# PC5_AudioOutput.net
KiCad netlist of a schematic drawn in Altium Designer
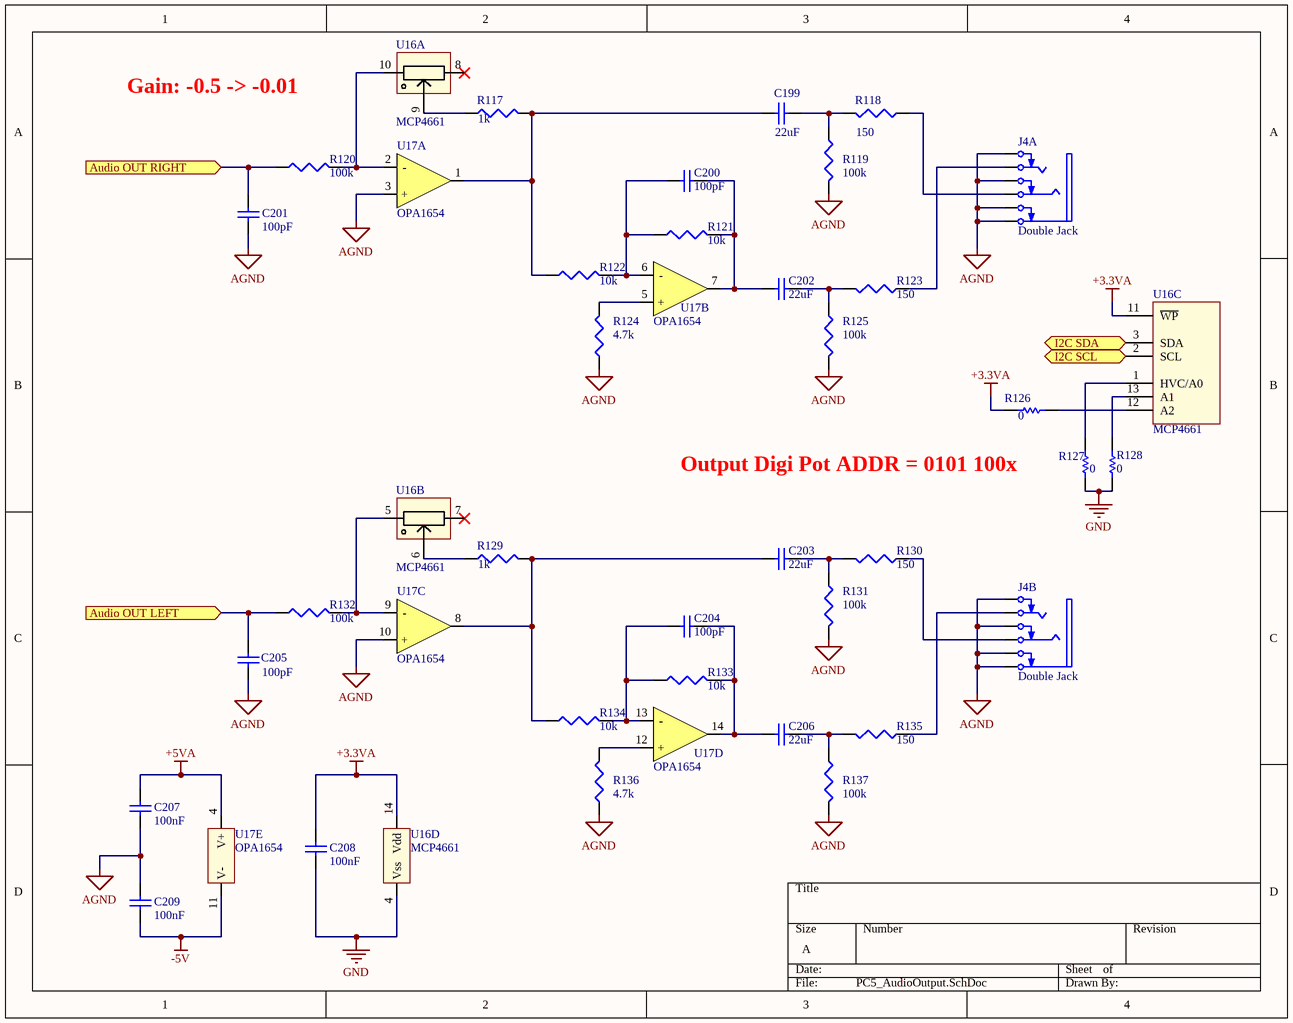
[diagram p0: PC5_AudioOutput.SchDoc]

(export (version "E")
  (design (tool "Eeschema 10.0.6"))
  (components
    (comp (ref "C199")
      (value "22uF")
      (footprint "CAPC1608X08")
      (description "Capacitor")
      (fields (field (name "Comment") "Cap 22uF"))
      (libsource (lib "Michel") (part "Cap Semi"))
    )
    (comp (ref "C200")
      (value "100pF")
      (footprint "CAPC1608X08")
      (description "Capacitor")
      (fields (field (name "Comment") "Cap 100pF"))
      (libsource (lib "Michel") (part "Cap Semi"))
    )
    (comp (ref "C201")
      (value "100pF")
      (footprint "CAPC1608X08")
      (description "Capacitor")
      (fields (field (name "Comment") "Cap 100pF"))
      (libsource (lib "Michel") (part "Cap Semi"))
    )
    (comp (ref "C202")
      (value "22uF")
      (footprint "CAPC1608X08")
      (description "Capacitor")
      (fields (field (name "Comment") "Cap 22uF"))
      (libsource (lib "Michel") (part "Cap Semi"))
    )
    (comp (ref "C203")
      (value "22uF")
      (footprint "CAPC1608X08")
      (description "Capacitor")
      (fields (field (name "Comment") "Cap 22uF"))
      (libsource (lib "Michel") (part "Cap Semi"))
    )
    (comp (ref "C204")
      (value "100pF")
      (footprint "CAPC1608X08")
      (description "Capacitor")
      (fields (field (name "Comment") "Cap 100pF"))
      (libsource (lib "Michel") (part "Cap Semi"))
    )
    (comp (ref "C205")
      (value "100pF")
      (footprint "CAPC1608X08")
      (description "Capacitor")
      (fields (field (name "Comment") "Cap 100pF"))
      (libsource (lib "Michel") (part "Cap Semi"))
    )
    (comp (ref "C206")
      (value "22uF")
      (footprint "CAPC1608X08")
      (description "Capacitor")
      (fields (field (name "Comment") "Cap 22uF"))
      (libsource (lib "Michel") (part "Cap Semi"))
    )
    (comp (ref "C207")
      (value "100nF")
      (footprint "CAPC1608X08")
      (description "Capacitor")
      (fields (field (name "Comment") "Cap 100nF"))
      (libsource (lib "Michel") (part "Cap Semi"))
    )
    (comp (ref "C208")
      (value "100nF")
      (footprint "CAPC1608X08")
      (description "Capacitor")
      (fields (field (name "Comment") "Cap 100nF"))
      (libsource (lib "Michel") (part "Cap Semi"))
    )
    (comp (ref "C209")
      (value "100nF")
      (footprint "CAPC1608X08")
      (description "Capacitor")
      (fields (field (name "Comment") "Cap 100nF"))
      (libsource (lib "Michel") (part "Cap Semi"))
    )
    (comp (ref "J4")
      (value "Double Jack")
      (footprint "Amphenol_ACJS-MHDC")
      (description "Dual Jack stereo bypassed")
      (libsource (lib "") (part "Dual TRS Jack Bypassed_1"))
    )
    (comp (ref "R117")
      (value "1k")
      (footprint "RESC1608X05")
      (description "Resistor")
      (fields (field (name "Comment") "Res 1k"))
      (libsource (lib "Michel") (part "Res3"))
    )
    (comp (ref "R118")
      (value "150")
      (footprint "RESC1608X05")
      (description "Capacitor")
      (fields (field (name "Comment") "Cap 150"))
      (libsource (lib "Michel") (part "Res3"))
    )
    (comp (ref "R119")
      (value "100k")
      (footprint "RESC1608X05")
      (description "Resistor")
      (fields (field (name "Comment") "Res 100k"))
      (libsource (lib "Michel") (part "Res3"))
    )
    (comp (ref "R120")
      (value "100k")
      (footprint "RESC1608X05")
      (description "Resistor")
      (fields (field (name "Comment") "Res 100k"))
      (libsource (lib "Michel") (part "Res3"))
    )
    (comp (ref "R121")
      (value "10k")
      (footprint "RESC1608X05")
      (description "Resistor")
      (fields (field (name "Comment") "Res 10k"))
      (libsource (lib "Michel") (part "Res3"))
    )
    (comp (ref "R122")
      (value "10k")
      (footprint "RESC1608X05")
      (description "Resistor")
      (fields (field (name "Comment") "Res 10k"))
      (libsource (lib "Michel") (part "Res3"))
    )
    (comp (ref "R123")
      (value "150")
      (footprint "RESC1608X05")
      (description "Capacitor")
      (fields (field (name "Comment") "Cap 150"))
      (libsource (lib "Michel") (part "Res3"))
    )
    (comp (ref "R124")
      (value "4.7k")
      (footprint "RESC1608X05")
      (description "Resistor")
      (fields (field (name "Comment") "Res 4.7k"))
      (libsource (lib "Michel") (part "Res3"))
    )
    (comp (ref "R125")
      (value "100k")
      (footprint "RESC1608X05")
      (description "Resistor")
      (fields (field (name "Comment") "Res 100k"))
      (libsource (lib "Michel") (part "Res3"))
    )
    (comp (ref "R126")
      (value "0")
      (footprint "RESC1608X05")
      (description "Resistor")
      (fields (field (name "Comment") "Res 0 Ohm"))
      (libsource (lib "Michel") (part "Res1"))
    )
    (comp (ref "R127")
      (value "0")
      (footprint "RESC1608X05")
      (description "Resistor")
      (fields (field (name "Comment") "Res 0 Ohm"))
      (libsource (lib "Michel") (part "Res1"))
    )
    (comp (ref "R128")
      (value "0")
      (footprint "RESC1608X05")
      (description "Resistor")
      (fields (field (name "Comment") "Res 0 Ohm"))
      (libsource (lib "Michel") (part "Res1"))
    )
    (comp (ref "R129")
      (value "1k")
      (footprint "RESC1608X05")
      (description "Resistor")
      (fields (field (name "Comment") "Res 1k"))
      (libsource (lib "Michel") (part "Res3"))
    )
    (comp (ref "R130")
      (value "150")
      (footprint "RESC1608X05")
      (description "Capacitor")
      (fields (field (name "Comment") "Cap 150"))
      (libsource (lib "Michel") (part "Res3"))
    )
    (comp (ref "R131")
      (value "100k")
      (footprint "RESC1608X05")
      (description "Resistor")
      (fields (field (name "Comment") "Res 100k"))
      (libsource (lib "Michel") (part "Res3"))
    )
    (comp (ref "R132")
      (value "100k")
      (footprint "RESC1608X05")
      (description "Resistor")
      (fields (field (name "Comment") "Res 100k"))
      (libsource (lib "Michel") (part "Res3"))
    )
    (comp (ref "R133")
      (value "10k")
      (footprint "RESC1608X05")
      (description "Resistor")
      (fields (field (name "Comment") "Res 10k"))
      (libsource (lib "Michel") (part "Res3"))
    )
    (comp (ref "R134")
      (value "10k")
      (footprint "RESC1608X05")
      (description "Resistor")
      (fields (field (name "Comment") "Res 10k"))
      (libsource (lib "Michel") (part "Res3"))
    )
    (comp (ref "R135")
      (value "150")
      (footprint "RESC1608X05")
      (description "Capacitor")
      (fields (field (name "Comment") "Cap 150"))
      (libsource (lib "Michel") (part "Res3"))
    )
    (comp (ref "R136")
      (value "4.7k")
      (footprint "RESC1608X05")
      (description "Resistor")
      (fields (field (name "Comment") "Res 4.7k"))
      (libsource (lib "Michel") (part "Res3"))
    )
    (comp (ref "R137")
      (value "100k")
      (footprint "RESC1608X05")
      (description "Resistor")
      (fields (field (name "Comment") "Res 100k"))
      (libsource (lib "Michel") (part "Res3"))
    )
    (comp (ref "U16")
      (value "MCP4661")
      (footprint "TSSOP14_MC-M")
      (description "Dual DigiPot non volatile I2C")
      (libsource (lib "") (part "MCP4661_1"))
    )
    (comp (ref "U17")
      (value "OPA1654")
      (footprint "D14-M")
      (description "Quad Audio OpAmp")
      (libsource (lib "") (part "OPA1654_1"))
    )
  )
  (nets
    (net (code "1") (name "+3.3VA") (class "Default")
      (node (ref "C208") (pin "1") (pinfunction "1_1") (pintype "passive"))
      (node (ref "R126") (pin "1") (pinfunction "1_1") (pintype "passive"))
      (node (ref "U16") (pin "11") (pinfunction "~{WP}_11") (pintype "passive"))
      (node (ref "U16") (pin "14") (pinfunction "Vdd_14") (pintype "power_in"))
    )
    (net (code "2") (name "+5VA") (class "Default")
      (node (ref "C207") (pin "1") (pinfunction "1_1") (pintype "passive"))
      (node (ref "U17") (pin "4") (pinfunction "V+_4") (pintype "power_in"))
    )
    (net (code "3") (name "-5V") (class "Default")
      (node (ref "C209") (pin "2") (pinfunction "2_2") (pintype "passive"))
      (node (ref "U17") (pin "11") (pinfunction "V-_11") (pintype "power_in"))
    )
    (net (code "4") (name "/Audio OUT LEFT") (class "Default")
      (node (ref "C205") (pin "2") (pinfunction "2_2") (pintype "passive"))
      (node (ref "R132") (pin "1") (pinfunction "1_1") (pintype "passive"))
    )
    (net (code "5") (name "/Audio OUT RIGHT") (class "Default")
      (node (ref "C201") (pin "2") (pinfunction "2_2") (pintype "passive"))
      (node (ref "R120") (pin "1") (pinfunction "1_1") (pintype "passive"))
    )
    (net (code "6") (name "/I2C SCL") (class "Default")
      (node (ref "U16") (pin "2") (pinfunction "SCL_2") (pintype "passive"))
    )
    (net (code "7") (name "/I2C SDA") (class "Default")
      (node (ref "U16") (pin "3") (pinfunction "SDA_3") (pintype "passive"))
    )
    (net (code "8") (name "AGND") (class "Default")
      (node (ref "C201") (pin "1") (pinfunction "1_1") (pintype "passive"))
      (node (ref "C205") (pin "1") (pinfunction "1_1") (pintype "passive"))
      (node (ref "C207") (pin "2") (pinfunction "2_2") (pintype "passive"))
      (node (ref "C209") (pin "1") (pinfunction "1_1") (pintype "passive"))
      (node (ref "J4") (pin "1") (pinfunction "SB_1") (pintype "passive"))
      (node (ref "J4") (pin "10") (pinfunction "S_10") (pintype "power_in"))
      (node (ref "J4") (pin "2") (pinfunction "RB_2") (pintype "passive"))
      (node (ref "J4") (pin "3") (pinfunction "TB_3") (pintype "passive"))
      (node (ref "J4") (pin "4") (pinfunction "S_4") (pintype "power_in"))
      (node (ref "J4") (pin "7") (pinfunction "SB_7") (pintype "passive"))
      (node (ref "J4") (pin "8") (pinfunction "RB_8") (pintype "passive"))
      (node (ref "J4") (pin "9") (pinfunction "TB_9") (pintype "passive"))
      (node (ref "R119") (pin "2") (pinfunction "2_2") (pintype "passive"))
      (node (ref "R124") (pin "1") (pinfunction "1_1") (pintype "passive"))
      (node (ref "R125") (pin "2") (pinfunction "2_2") (pintype "passive"))
      (node (ref "R131") (pin "2") (pinfunction "2_2") (pintype "passive"))
      (node (ref "R136") (pin "1") (pinfunction "1_1") (pintype "passive"))
      (node (ref "R137") (pin "2") (pinfunction "2_2") (pintype "passive"))
      (node (ref "U17") (pin "10") (pinfunction "+_10") (pintype "passive"))
      (node (ref "U17") (pin "3") (pinfunction "+_3") (pintype "passive"))
    )
    (net (code "9") (name "GND") (class "Default")
      (node (ref "C208") (pin "2") (pinfunction "2_2") (pintype "passive"))
      (node (ref "R127") (pin "1") (pinfunction "1_1") (pintype "passive"))
      (node (ref "R128") (pin "1") (pinfunction "1_1") (pintype "passive"))
      (node (ref "U16") (pin "4") (pinfunction "Vss_4") (pintype "power_in"))
    )
    (net (code "10") (name "Net-(C199-Pad1)") (class "Default")
      (node (ref "C199") (pin "1") (pinfunction "1_1") (pintype "passive"))
      (node (ref "R118") (pin "2") (pinfunction "2_2") (pintype "passive"))
      (node (ref "R119") (pin "1") (pinfunction "1_1") (pintype "passive"))
    )
    (net (code "11") (name "Net-(C202-Pad1)") (class "Default")
      (node (ref "C202") (pin "1") (pinfunction "1_1") (pintype "passive"))
      (node (ref "R123") (pin "2") (pinfunction "2_2") (pintype "passive"))
      (node (ref "R125") (pin "1") (pinfunction "1_1") (pintype "passive"))
    )
    (net (code "12") (name "Net-(C203-Pad1)") (class "Default")
      (node (ref "C203") (pin "1") (pinfunction "1_1") (pintype "passive"))
      (node (ref "R130") (pin "2") (pinfunction "2_2") (pintype "passive"))
      (node (ref "R131") (pin "1") (pinfunction "1_1") (pintype "passive"))
    )
    (net (code "13") (name "Net-(C206-Pad1)") (class "Default")
      (node (ref "C206") (pin "1") (pinfunction "1_1") (pintype "passive"))
      (node (ref "R135") (pin "2") (pinfunction "2_2") (pintype "passive"))
      (node (ref "R137") (pin "1") (pinfunction "1_1") (pintype "passive"))
    )
    (net (code "14") (name "Net-(J4A-R)") (class "Default")
      (node (ref "J4") (pin "11") (pinfunction "R_11") (pintype "passive"))
      (node (ref "R118") (pin "1") (pinfunction "1_1") (pintype "passive"))
    )
    (net (code "15") (name "Net-(J4A-T)") (class "Default")
      (node (ref "J4") (pin "12") (pinfunction "T_12") (pintype "passive"))
      (node (ref "R123") (pin "1") (pinfunction "1_1") (pintype "passive"))
    )
    (net (code "16") (name "Net-(J4B-R)") (class "Default")
      (node (ref "J4") (pin "5") (pinfunction "R_5") (pintype "passive"))
      (node (ref "R130") (pin "1") (pinfunction "1_1") (pintype "passive"))
    )
    (net (code "17") (name "Net-(J4B-T)") (class "Default")
      (node (ref "J4") (pin "6") (pinfunction "T_6") (pintype "passive"))
      (node (ref "R135") (pin "1") (pinfunction "1_1") (pintype "passive"))
    )
    (net (code "18") (name "Net-(U16A-P0B)") (class "Default")
      (node (ref "R120") (pin "2") (pinfunction "2_2") (pintype "passive"))
      (node (ref "U16") (pin "10") (pinfunction "P0B_10") (pintype "passive"))
      (node (ref "U17") (pin "2") (pinfunction "-_2") (pintype "passive"))
    )
    (net (code "19") (name "Net-(U16A-P0W)") (class "Default")
      (node (ref "R117") (pin "1") (pinfunction "1_1") (pintype "passive"))
      (node (ref "U16") (pin "9") (pinfunction "P0W_9") (pintype "passive"))
    )
    (net (code "20") (name "Net-(U16B-P1B)") (class "Default")
      (node (ref "R132") (pin "2") (pinfunction "2_2") (pintype "passive"))
      (node (ref "U16") (pin "5") (pinfunction "P1B_5") (pintype "passive"))
      (node (ref "U17") (pin "9") (pinfunction "-_9") (pintype "passive"))
    )
    (net (code "21") (name "Net-(U16B-P1W)") (class "Default")
      (node (ref "R129") (pin "1") (pinfunction "1_1") (pintype "passive"))
      (node (ref "U16") (pin "6") (pinfunction "P1W_6") (pintype "passive"))
    )
    (net (code "22") (name "Net-(U16C-A1)") (class "Default")
      (node (ref "R128") (pin "2") (pinfunction "2_2") (pintype "passive"))
      (node (ref "U16") (pin "13") (pinfunction "A1_13") (pintype "power_in"))
    )
    (net (code "23") (name "Net-(U16C-A2)") (class "Default")
      (node (ref "R126") (pin "2") (pinfunction "2_2") (pintype "passive"))
      (node (ref "U16") (pin "12") (pinfunction "A2_12") (pintype "power_in"))
    )
    (net (code "24") (name "Net-(U16C-HVC{slash}A0)") (class "Default")
      (node (ref "R127") (pin "2") (pinfunction "2_2") (pintype "passive"))
      (node (ref "U16") (pin "1") (pinfunction "HVC/A0_1") (pintype "power_in"))
    )
    (net (code "25") (name "Net-(U17A-OUT)") (class "Default")
      (node (ref "C199") (pin "2") (pinfunction "2_2") (pintype "passive"))
      (node (ref "R117") (pin "2") (pinfunction "2_2") (pintype "passive"))
      (node (ref "R122") (pin "1") (pinfunction "1_1") (pintype "passive"))
      (node (ref "U17") (pin "1") (pinfunction "OUT_1") (pintype "passive"))
    )
    (net (code "26") (name "Net-(U17B-+)") (class "Default")
      (node (ref "R124") (pin "2") (pinfunction "2_2") (pintype "passive"))
      (node (ref "U17") (pin "5") (pinfunction "+_5") (pintype "passive"))
    )
    (net (code "27") (name "Net-(U17B--)") (class "Default")
      (node (ref "C200") (pin "2") (pinfunction "2_2") (pintype "passive"))
      (node (ref "R121") (pin "1") (pinfunction "1_1") (pintype "passive"))
      (node (ref "R122") (pin "2") (pinfunction "2_2") (pintype "passive"))
      (node (ref "U17") (pin "6") (pinfunction "-_6") (pintype "passive"))
    )
    (net (code "28") (name "Net-(U17B-OUT)") (class "Default")
      (node (ref "C200") (pin "1") (pinfunction "1_1") (pintype "passive"))
      (node (ref "C202") (pin "2") (pinfunction "2_2") (pintype "passive"))
      (node (ref "R121") (pin "2") (pinfunction "2_2") (pintype "passive"))
      (node (ref "U17") (pin "7") (pinfunction "OUT_7") (pintype "passive"))
    )
    (net (code "29") (name "Net-(U17C-OUT)") (class "Default")
      (node (ref "C203") (pin "2") (pinfunction "2_2") (pintype "passive"))
      (node (ref "R129") (pin "2") (pinfunction "2_2") (pintype "passive"))
      (node (ref "R134") (pin "1") (pinfunction "1_1") (pintype "passive"))
      (node (ref "U17") (pin "8") (pinfunction "OUT_8") (pintype "passive"))
    )
    (net (code "30") (name "Net-(U17D-+)") (class "Default")
      (node (ref "R136") (pin "2") (pinfunction "2_2") (pintype "passive"))
      (node (ref "U17") (pin "12") (pinfunction "+_12") (pintype "passive"))
    )
    (net (code "31") (name "Net-(U17D--)") (class "Default")
      (node (ref "C204") (pin "2") (pinfunction "2_2") (pintype "passive"))
      (node (ref "R133") (pin "1") (pinfunction "1_1") (pintype "passive"))
      (node (ref "R134") (pin "2") (pinfunction "2_2") (pintype "passive"))
      (node (ref "U17") (pin "13") (pinfunction "-_13") (pintype "passive"))
    )
    (net (code "32") (name "Net-(U17D-OUT)") (class "Default")
      (node (ref "C204") (pin "1") (pinfunction "1_1") (pintype "passive"))
      (node (ref "C206") (pin "2") (pinfunction "2_2") (pintype "passive"))
      (node (ref "R133") (pin "2") (pinfunction "2_2") (pintype "passive"))
      (node (ref "U17") (pin "14") (pinfunction "OUT_14") (pintype "passive"))
    )
    (net (code "33") (name "unconnected-(U16A-P0A-Pad8)") (class "Default")
      (node (ref "U16") (pin "8") (pinfunction "P0A_8") (pintype "passive+no_connect"))
    )
    (net (code "34") (name "unconnected-(U16B-P1A-Pad7)") (class "Default")
      (node (ref "U16") (pin "7") (pinfunction "P1A_7") (pintype "passive+no_connect"))
    )
  )
)
